# untitled.net
KiCad netlist of a schematic drawn in EAGLE
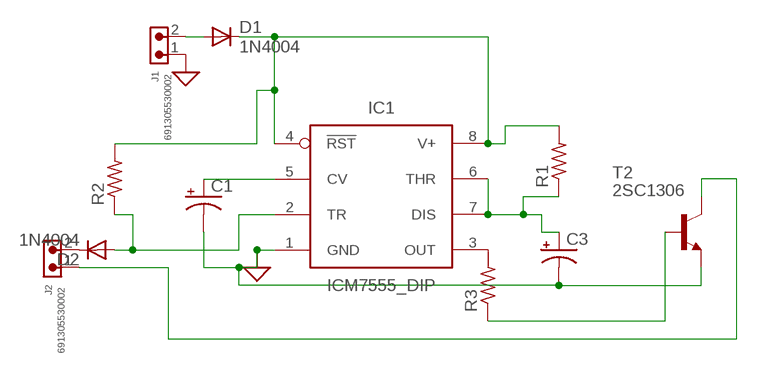
[diagram p0: schematic, sheet 1]

(export (version "E")
  (design (tool "Eeschema 10.0.6"))
  (components
    (comp (ref "C1")
      (value "CAPACITOR-PE2.5-5")
      (footprint "eagle-import:E2,5-5")
      (libsource (lib "eagle-import") (part "CAPACITOR-PE2.5-5"))
    )
    (comp (ref "C3")
      (value "CAPACITOR-PE2.5-5")
      (footprint "eagle-import:E2,5-5")
      (libsource (lib "eagle-import") (part "CAPACITOR-PE2.5-5"))
    )
    (comp (ref "D1")
      (value "1N4004")
      (footprint "eagle-import:DO41-10")
      (libsource (lib "eagle-import") (part "1N4004"))
    )
    (comp (ref "D2")
      (value "1N4004")
      (footprint "eagle-import:DO41-10")
      (libsource (lib "eagle-import") (part "1N4004"))
    )
    (comp (ref "IC1")
      (value "ICM7555_DIP")
      (footprint "eagle-import:DIP826W53P254L959H508Q8B")
      (fields
        (field (name "MANUFACTURER") "Renesas Electronics America Inc ")
        (field (name "MPN") "ICM7555IPAZ ")
      )
      (libsource (lib "eagle-import") (part "555_DIPICM7"))
    )
    (comp (ref "J1")
      (value "691305530002")
      (footprint "eagle-import:691305530002")
      (libsource (lib "eagle-import") (part "691305530002"))
    )
    (comp (ref "J2")
      (value "691305530002")
      (footprint "eagle-import:691305530002")
      (libsource (lib "eagle-import") (part "691305530002"))
    )
    (comp (ref "R1")
      (value "R-US_0207/7")
      (footprint "eagle-import:0207_7")
      (libsource (lib "eagle-import") (part "adafruit_420_R-US_0207/7"))
    )
    (comp (ref "R2")
      (value "R-US_0207/7")
      (footprint "eagle-import:0207_7")
      (libsource (lib "eagle-import") (part "adafruit_420_R-US_0207/7"))
    )
    (comp (ref "R3")
      (value "R-US_0207/12")
      (footprint "eagle-import:0207_12")
      (libsource (lib "eagle-import") (part "R-US_0207/12"))
    )
    (comp (ref "T2")
      (value "2SC1306")
      (footprint "eagle-import:TO220BV")
      (libsource (lib "eagle-import") (part "2SC1306"))
    )
  )
  (nets
    (net (code "1") (name "Net-(D1-PadA)") (class "Default")
      (node (ref "D1") (pin "A") (pinfunction "A_A") (pintype "passive"))
      (node (ref "J1") (pin "2") (pinfunction "2_2") (pintype "passive"))
    )
    (net (code "2") (name "Net-(D2-PadC)") (class "Default")
      (node (ref "D2") (pin "C") (pinfunction "C_C") (pintype "passive"))
      (node (ref "J2") (pin "2") (pinfunction "2_2") (pintype "passive"))
    )
    (net (code "3") (name "Net-(IC1-CV)") (class "Default")
      (node (ref "C1") (pin "+") (pinfunction "+_+") (pintype "passive"))
      (node (ref "IC1") (pin "5") (pinfunction "CV_5") (pintype "input"))
    )
    (net (code "4") (name "Net-(IC1-DIS)") (class "Default")
      (node (ref "C3") (pin "+") (pinfunction "+_+") (pintype "passive"))
      (node (ref "IC1") (pin "6") (pinfunction "THR_6") (pintype "input"))
      (node (ref "IC1") (pin "7") (pinfunction "DIS_7") (pintype "input"))
      (node (ref "R1") (pin "1") (pinfunction "1_1") (pintype "passive"))
    )
    (net (code "5") (name "Net-(IC1-OUT)") (class "Default")
      (node (ref "IC1") (pin "3") (pinfunction "OUT_3") (pintype "output"))
      (node (ref "R3") (pin "2") (pinfunction "2_2") (pintype "passive"))
    )
    (net (code "6") (name "Net-(IC1-TR)") (class "Default")
      (node (ref "D2") (pin "A") (pinfunction "A_A") (pintype "passive"))
      (node (ref "IC1") (pin "2") (pinfunction "TR_2") (pintype "input"))
      (node (ref "R2") (pin "1") (pinfunction "1_1") (pintype "passive"))
    )
    (net (code "7") (name "Net-(IC1-V+)") (class "Default")
      (node (ref "D1") (pin "C") (pinfunction "C_C") (pintype "passive"))
      (node (ref "IC1") (pin "4") (pinfunction "~{RST}_4") (pintype "input"))
      (node (ref "IC1") (pin "8") (pinfunction "V+_8") (pintype "power_in"))
      (node (ref "R1") (pin "2") (pinfunction "2_2") (pintype "passive"))
      (node (ref "R2") (pin "2") (pinfunction "2_2") (pintype "passive"))
    )
    (net (code "8") (name "Net-(T2-B)") (class "Default")
      (node (ref "R3") (pin "1") (pinfunction "1_1") (pintype "passive"))
      (node (ref "T2") (pin "1") (pinfunction "B_1") (pintype "passive"))
    )
    (net (code "9") (name "Net-(T2-C)") (class "Default")
      (node (ref "J2") (pin "1") (pinfunction "1_1") (pintype "passive"))
      (node (ref "T2") (pin "2") (pinfunction "C_2") (pintype "passive"))
    )
    (net (code "10") (name "SUP") (class "Default")
      (node (ref "C1") (pin "-") (pinfunction "-_-") (pintype "passive"))
      (node (ref "C3") (pin "-") (pinfunction "-_-") (pintype "passive"))
      (node (ref "IC1") (pin "1") (pinfunction "GND_1") (pintype "power_in"))
      (node (ref "J1") (pin "1") (pinfunction "1_1") (pintype "passive"))
      (node (ref "T2") (pin "3") (pinfunction "E_3") (pintype "passive"))
    )
  )
)
